# Sheet1.net
KiCad netlist of a schematic drawn in Altium Designer
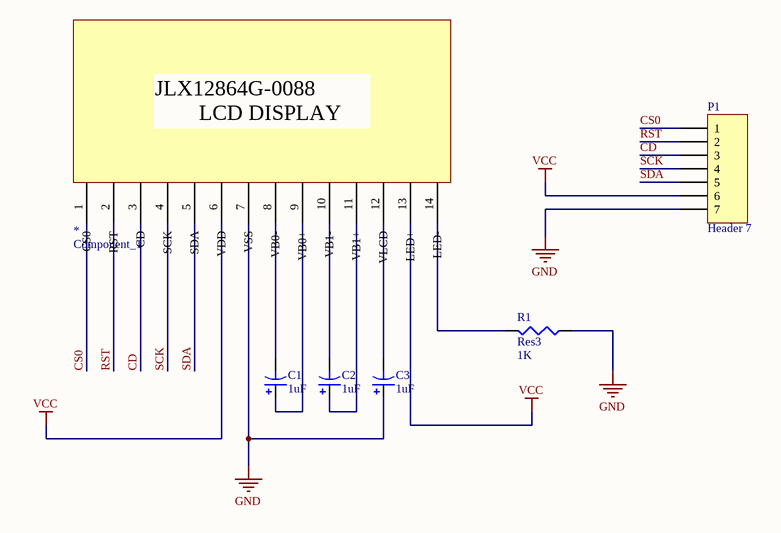
[diagram p0: Sheet1.SchDoc]

(export (version "E")
  (design (tool "Eeschema 10.0.6"))
  (components
    (comp (ref "*")
      (value "Component_1")
      (footprint "PCBComponent_1")
      (libsource (lib "JLX12864g0088") (part "Component_1"))
    )
    (comp (ref "C1")
      (value "1uF")
      (footprint "C0805")
      (description "Polarized Capacitor (Surface Mount)")
      (fields (field (name "Comment") "Cap Pol3") (field (name "PUBLISHER") "Altium Limited"))
      (libsource (lib "Miscellaneous Devices") (part "Cap Pol3"))
    )
    (comp (ref "C2")
      (value "1uF")
      (footprint "C0805")
      (description "Polarized Capacitor (Surface Mount)")
      (fields (field (name "Comment") "Cap Pol3") (field (name "PUBLISHER") "Altium Limited"))
      (libsource (lib "Miscellaneous Devices") (part "Cap Pol3"))
    )
    (comp (ref "C3")
      (value "1uF")
      (footprint "C0805")
      (description "Polarized Capacitor (Surface Mount)")
      (fields (field (name "Comment") "Cap Pol3") (field (name "PUBLISHER") "Altium Limited"))
      (libsource (lib "Miscellaneous Devices") (part "Cap Pol3"))
    )
    (comp (ref "P1")
      (value "Header 7")
      (footprint "HDR1X7")
      (description "Header, 7-Pin")
      (fields (field (name "PUBLISHER") "Altium Limited"))
      (libsource (lib "Miscellaneous Connectors") (part "Header 7"))
    )
    (comp (ref "R1")
      (value "Res3")
      (footprint "J1-0603")
      (description "Resistor")
      (fields (field (name "ALTIUM_VALUE") "1K") (field (name "PUBLISHER") "Altium Limited"))
      (libsource (lib "Miscellaneous Devices") (part "Res3"))
    )
  )
  (nets
    (net (code "1") (name "/CD") (class "Default")
      (node (ref "*") (pin "3") (pinfunction "CD_3") (pintype "passive"))
      (node (ref "P1") (pin "3") (pinfunction "3_3") (pintype "passive"))
    )
    (net (code "2") (name "/CS0") (class "Default")
      (node (ref "*") (pin "1") (pinfunction "CS0_1") (pintype "passive"))
      (node (ref "P1") (pin "1") (pinfunction "1_1") (pintype "passive"))
    )
    (net (code "3") (name "/RST") (class "Default")
      (node (ref "*") (pin "2") (pinfunction "RST_2") (pintype "passive"))
      (node (ref "P1") (pin "2") (pinfunction "2_2") (pintype "passive"))
    )
    (net (code "4") (name "/SCK") (class "Default")
      (node (ref "*") (pin "4") (pinfunction "SCK_4") (pintype "passive"))
      (node (ref "P1") (pin "4") (pinfunction "4_4") (pintype "passive"))
    )
    (net (code "5") (name "/SDA") (class "Default")
      (node (ref "*") (pin "5") (pinfunction "SDA_5") (pintype "passive"))
      (node (ref "P1") (pin "5") (pinfunction "5_5") (pintype "passive"))
    )
    (net (code "6") (name "GND") (class "Default")
      (node (ref "*") (pin "7") (pinfunction "VSS_7") (pintype "passive"))
      (node (ref "C3") (pin "1") (pinfunction "1_1") (pintype "passive"))
      (node (ref "P1") (pin "7") (pinfunction "7_7") (pintype "passive"))
      (node (ref "R1") (pin "1") (pinfunction "1_1") (pintype "passive"))
    )
    (net (code "7") (name "Net-(*-LED-)") (class "Default")
      (node (ref "*") (pin "14") (pinfunction "LED-_14") (pintype "passive"))
      (node (ref "R1") (pin "2") (pinfunction "2_2") (pintype "passive"))
    )
    (net (code "8") (name "Net-(*-VB0+)") (class "Default")
      (node (ref "*") (pin "9") (pinfunction "VB0+_9") (pintype "passive"))
      (node (ref "C1") (pin "1") (pinfunction "1_1") (pintype "passive"))
    )
    (net (code "9") (name "Net-(*-VB0-)") (class "Default")
      (node (ref "*") (pin "8") (pinfunction "VB0-_8") (pintype "passive"))
      (node (ref "C1") (pin "2") (pinfunction "2_2") (pintype "passive"))
    )
    (net (code "10") (name "Net-(*-VB1+)") (class "Default")
      (node (ref "*") (pin "11") (pinfunction "VB1+_11") (pintype "passive"))
      (node (ref "C2") (pin "1") (pinfunction "1_1") (pintype "passive"))
    )
    (net (code "11") (name "Net-(*-VB1-)") (class "Default")
      (node (ref "*") (pin "10") (pinfunction "VB1-_10") (pintype "passive"))
      (node (ref "C2") (pin "2") (pinfunction "2_2") (pintype "passive"))
    )
    (net (code "12") (name "Net-(*-VLCD)") (class "Default")
      (node (ref "*") (pin "12") (pinfunction "VLCD_12") (pintype "passive"))
      (node (ref "C3") (pin "2") (pinfunction "2_2") (pintype "passive"))
    )
    (net (code "13") (name "VCC") (class "Default")
      (node (ref "*") (pin "13") (pinfunction "LED+_13") (pintype "passive"))
      (node (ref "*") (pin "6") (pinfunction "VDD_6") (pintype "passive"))
      (node (ref "P1") (pin "6") (pinfunction "6_6") (pintype "passive"))
    )
  )
)
